# MR_UartConnector.net
KiCad netlist of a schematic drawn in Altium Designer
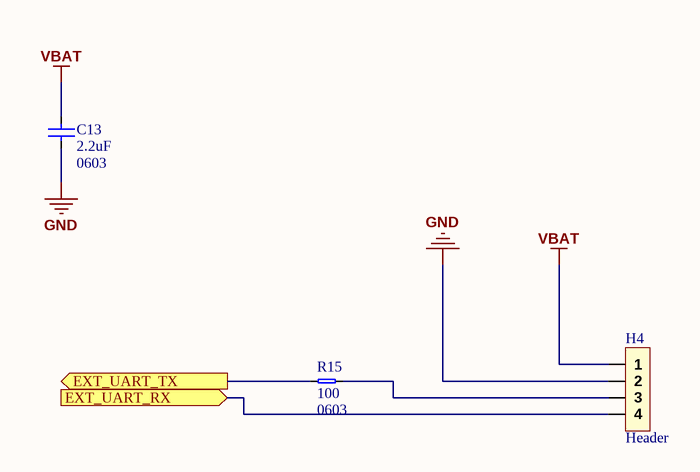
[diagram p0: MR_UartConnector.SchDoc]

(export (version "E")
  (design (tool "Eeschema 10.0.6"))
  (components
    (comp (ref "C13")
      (value "2.2uF")
      (footprint "0603_CAP_LD")
      (description "Ceramic Capacitor")
      (fields (field (name "PACKAGE") "0603") (field (name "Comment") "CerCap"))
      (libsource (lib "MiniRobot") (part "CerCap"))
    )
    (comp (ref "H4")
      (value "Header")
      (footprint "HE14 1x4 Straight")
      (description "Header 4x1 PIns")
      (libsource (lib "MiniRobot") (part "Header_4x1"))
    )
    (comp (ref "R15")
      (value "100")
      (footprint "0603_RES_LD")
      (description "Resistor")
      (fields (field (name "PACKAGE") "0603"))
      (libsource (lib "MiniRobot") (part "Resistor"))
    )
  )
  (nets
    (net (code "1") (name "/EXT_UART_RX") (class "Default")
      (node (ref "H4") (pin "4") (pinfunction "4_4") (pintype "passive"))
    )
    (net (code "2") (name "/EXT_UART_TX") (class "Default")
      (node (ref "R15") (pin "1") (pinfunction "1_1") (pintype "passive"))
    )
    (net (code "3") (name "GND") (class "Default")
      (node (ref "C13") (pin "1") (pinfunction "1_1") (pintype "passive"))
      (node (ref "H4") (pin "2") (pinfunction "2_2") (pintype "passive"))
    )
    (net (code "4") (name "Net-(H4-Pad3)") (class "Default")
      (node (ref "H4") (pin "3") (pinfunction "3_3") (pintype "passive"))
      (node (ref "R15") (pin "2") (pinfunction "2_2") (pintype "passive"))
    )
    (net (code "5") (name "VBAT") (class "Default")
      (node (ref "C13") (pin "2") (pinfunction "2_2") (pintype "passive"))
      (node (ref "H4") (pin "1") (pinfunction "1_1") (pintype "passive"))
    )
  )
)
